# mcdm_v52.net
KiCad netlist of a schematic drawn in EAGLE
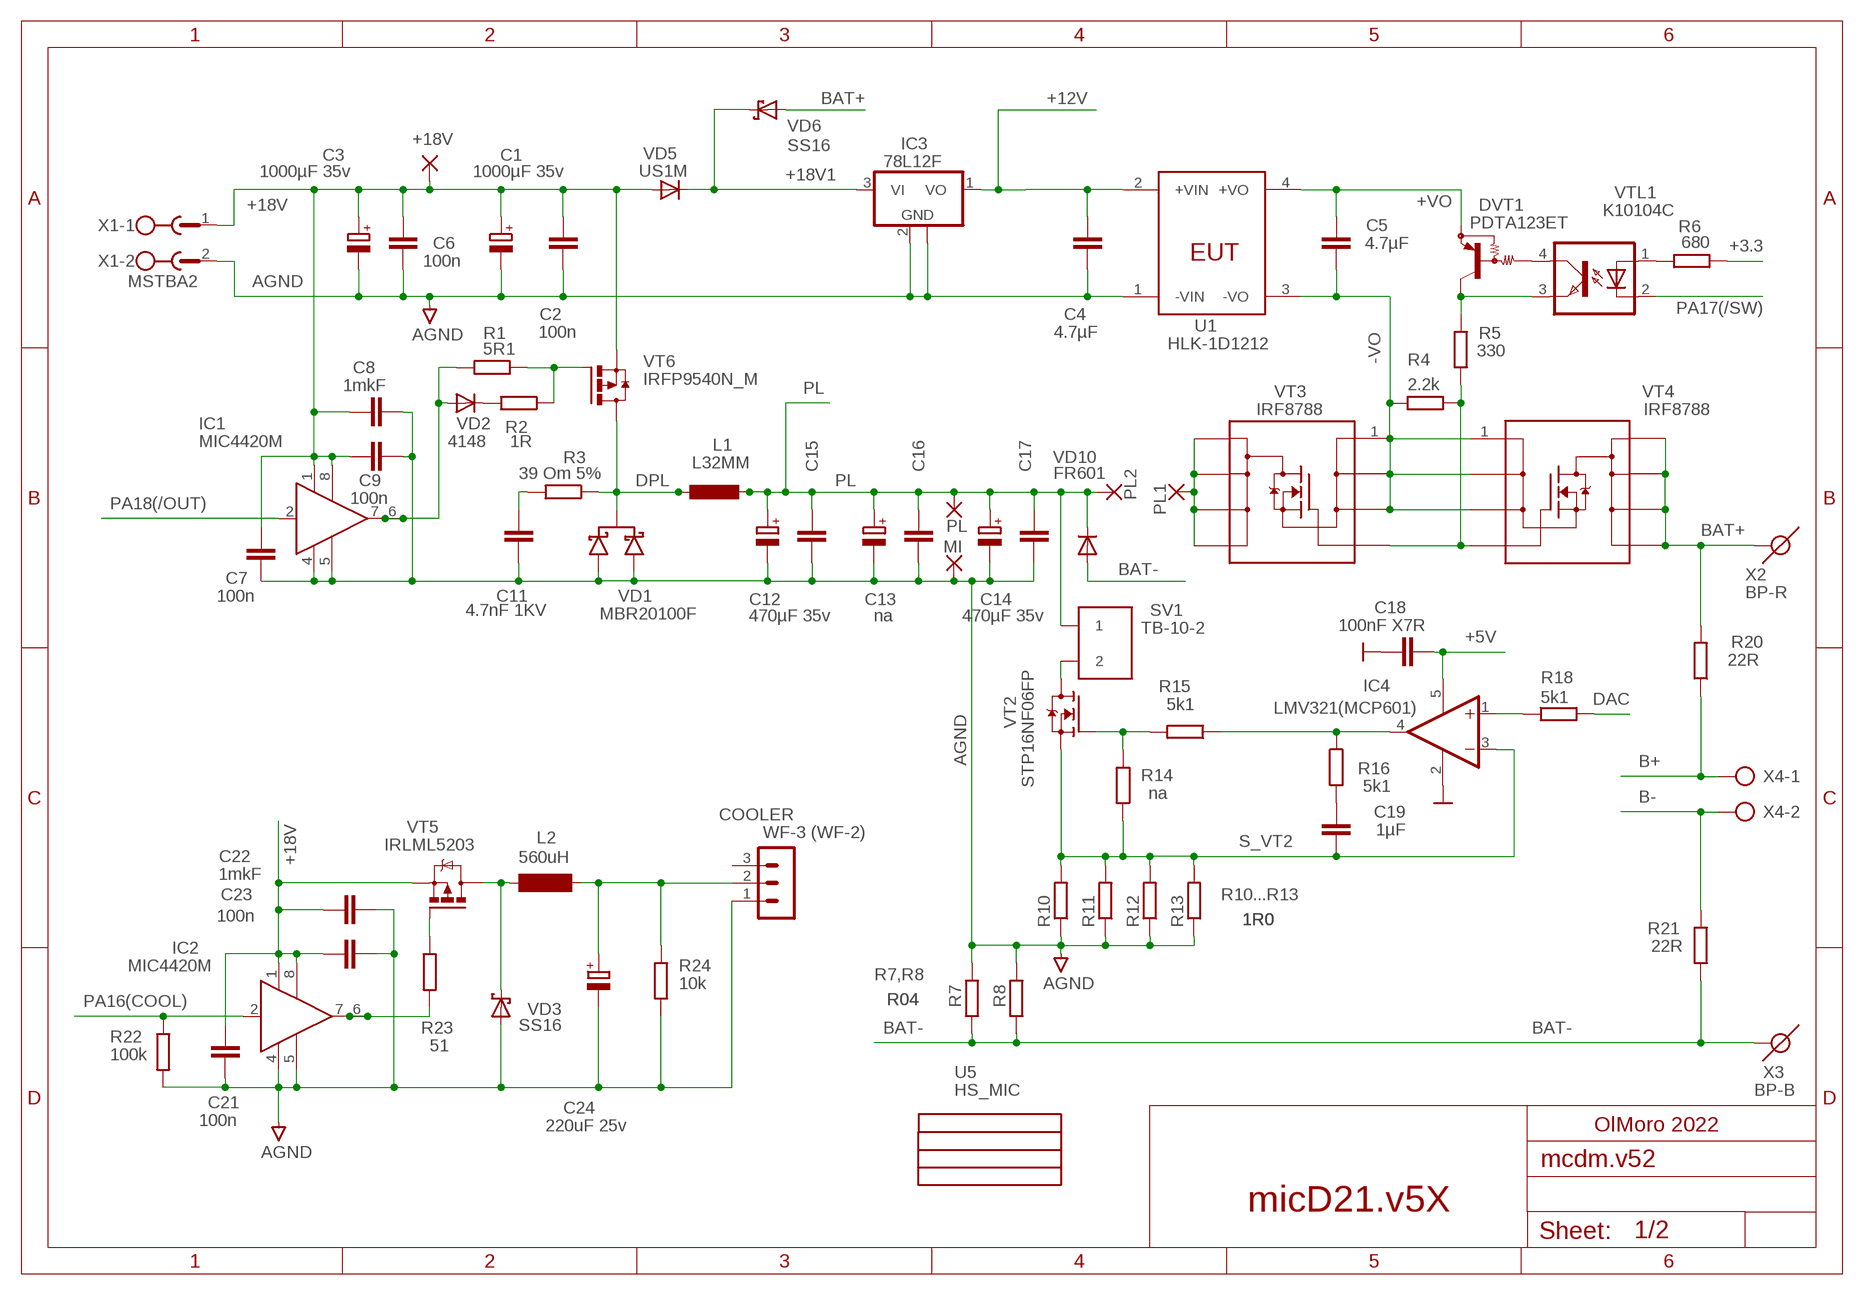
[diagram p0: schematic, sheet 1]
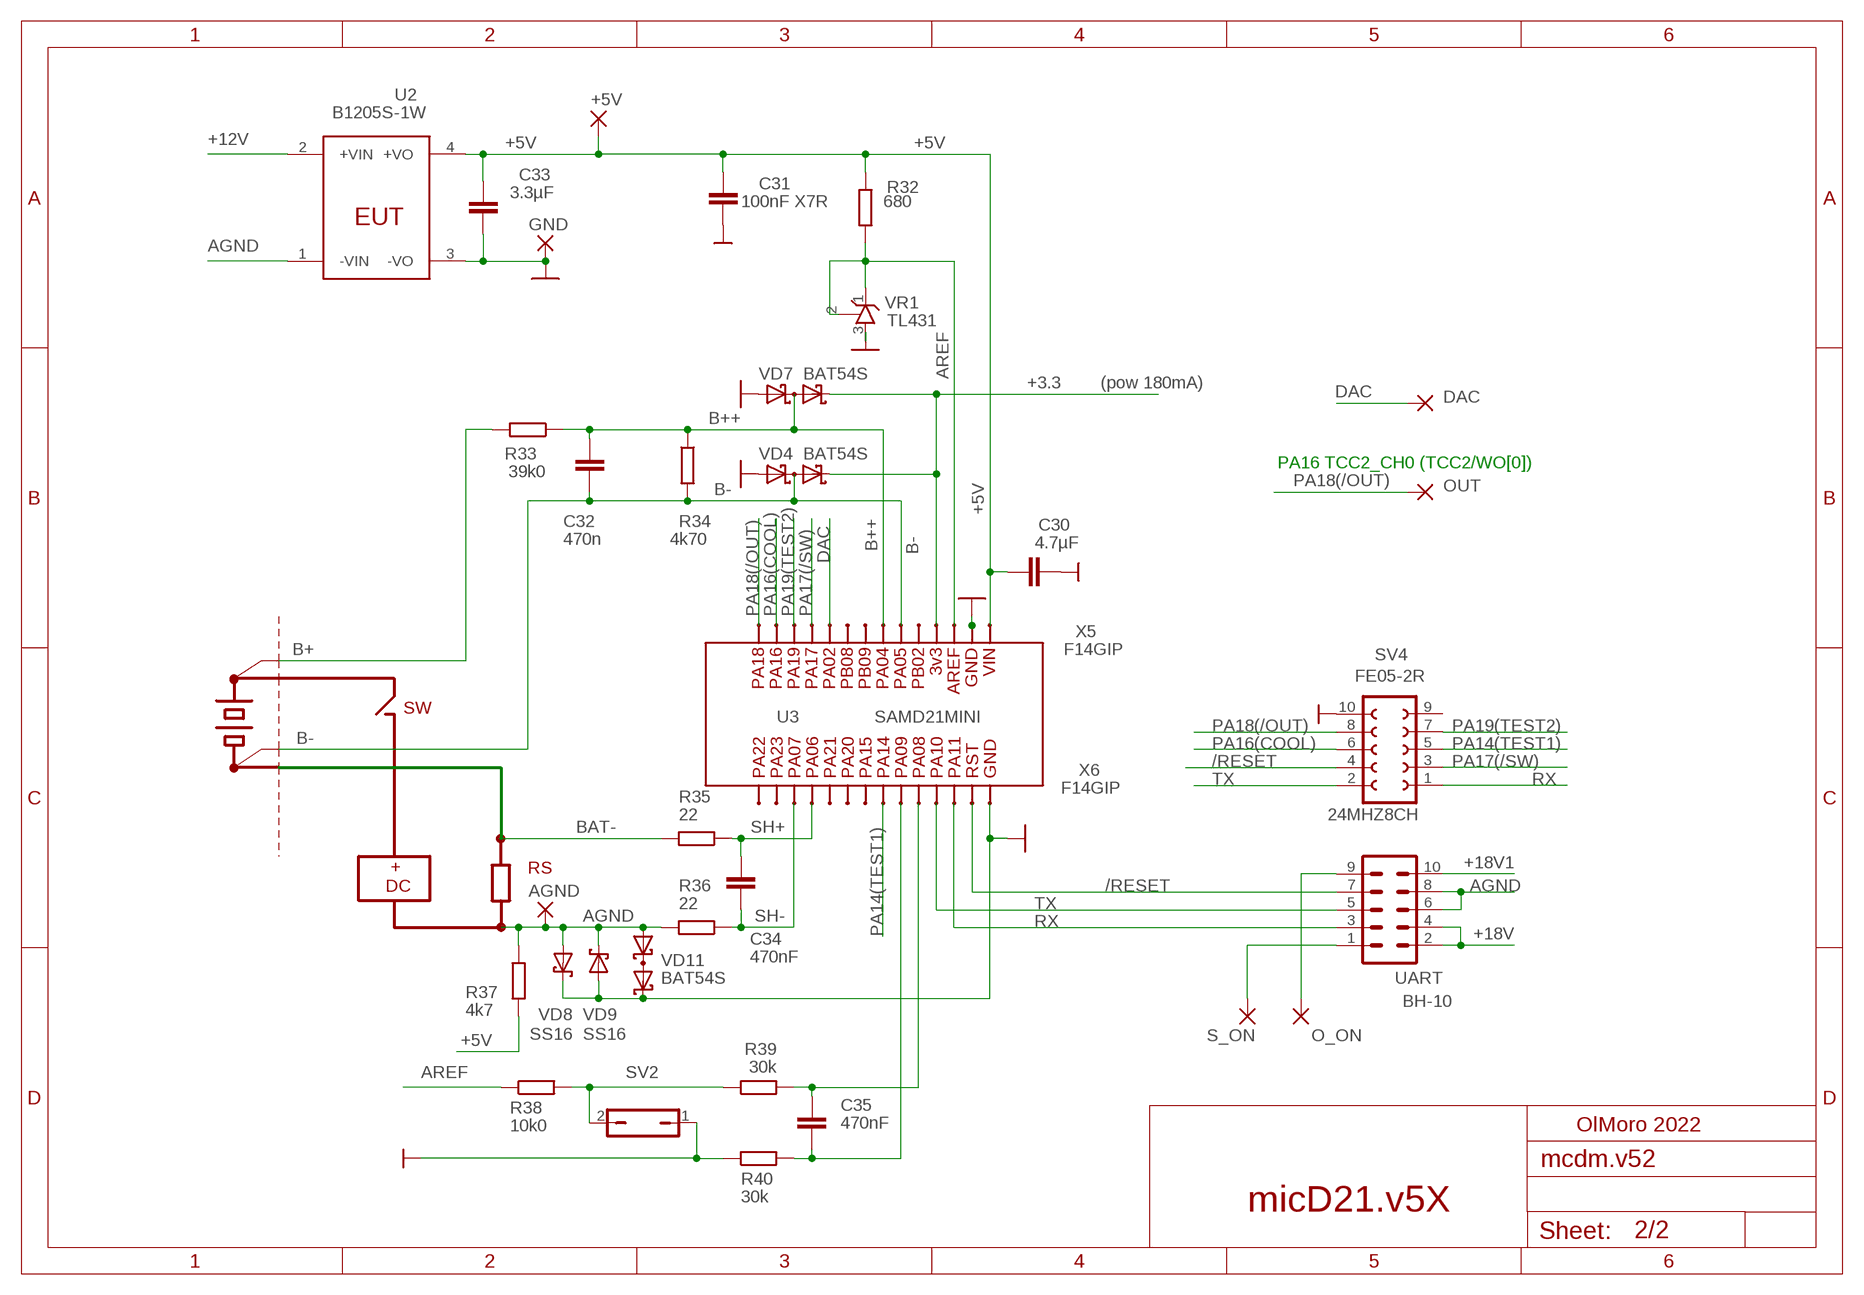
[diagram p1: schematic, sheet 2]

(export (version "E")
  (design (tool "Eeschema 10.0.6"))
  (components
    (comp (ref "+5V")
      (value "WIREPAD1,6/0,8")
      (footprint "eagle-import:1,6_0,8")
      (libsource (lib "eagle-import") (part "WIREPAD1,6/0,8"))
    )
    (comp (ref "24MHZ8CH")
      (value "DIAGNOSTICS")
      (footprint "eagle-import:DIAGNOSTICS")
      (libsource (lib "eagle-import") (part "DIAGNOSTICS"))
    )
    (comp (ref "AGND")
      (value "AGND")
      (footprint "eagle-import:4,16O1,6")
      (libsource (lib "eagle-import") (part "WIREPAD4,16O1,6"))
    )
    (comp (ref "C30")
      (value "4.7µF")
      (footprint "eagle-import:C0805")
      (libsource (lib "eagle-import") (part "C-EUC0805"))
    )
    (comp (ref "C31")
      (value "100nF X7R")
      (footprint "eagle-import:C0603")
      (libsource (lib "eagle-import") (part "C-EUC0603"))
    )
    (comp (ref "C32")
      (value "470n")
      (footprint "eagle-import:C0603")
      (libsource (lib "eagle-import") (part "C-EUC0603"))
    )
    (comp (ref "C33")
      (value "3.3µF")
      (footprint "eagle-import:C0805")
      (libsource (lib "eagle-import") (part "C-EUC0805"))
    )
    (comp (ref "C34")
      (value "470nF")
      (footprint "eagle-import:C0603")
      (libsource (lib "eagle-import") (part "C-EUC0603"))
    )
    (comp (ref "C35")
      (value "470nF")
      (footprint "eagle-import:C0603")
      (libsource (lib "eagle-import") (part "C-EUC0603"))
    )
    (comp (ref "DAC")
      (value "WIREPAD1,6/0,8")
      (footprint "eagle-import:1,6_0,8")
      (libsource (lib "eagle-import") (part "WIREPAD1,6/0,8"))
    )
    (comp (ref "GND")
      (value "GND")
      (footprint "eagle-import:4,16O1,6")
      (libsource (lib "eagle-import") (part "WIREPAD4,16O1,6"))
    )
    (comp (ref "OUT")
      (value "WIREPAD1,6/0,8")
      (footprint "eagle-import:1,6_0,8")
      (libsource (lib "eagle-import") (part "WIREPAD1,6/0,8"))
    )
    (comp (ref "O_ON")
      (value "WIREPAD1,6/0,8")
      (footprint "eagle-import:1,6_0,8")
      (libsource (lib "eagle-import") (part "WIREPAD1,6/0,8"))
    )
    (comp (ref "R32")
      (value "680")
      (footprint "eagle-import:R0603")
      (libsource (lib "eagle-import") (part "R-EU_R0603"))
    )
    (comp (ref "R33")
      (value "39k0")
      (footprint "eagle-import:R0603")
      (libsource (lib "eagle-import") (part "R-EU_R0603"))
    )
    (comp (ref "R34")
      (value "4k70")
      (footprint "eagle-import:R0603")
      (libsource (lib "eagle-import") (part "R-EU_R0603"))
    )
    (comp (ref "R35")
      (value "22")
      (footprint "eagle-import:R0603")
      (libsource (lib "eagle-import") (part "R-EU_R0603"))
    )
    (comp (ref "R36")
      (value "22")
      (footprint "eagle-import:R0603")
      (libsource (lib "eagle-import") (part "R-EU_R0603"))
    )
    (comp (ref "R37")
      (value "4k7")
      (footprint "eagle-import:R0603")
      (libsource (lib "eagle-import") (part "R-EU_R0603"))
    )
    (comp (ref "R38")
      (value "10k0")
      (footprint "eagle-import:R0603")
      (libsource (lib "eagle-import") (part "R-EU_R0603"))
    )
    (comp (ref "R39")
      (value "30k")
      (footprint "eagle-import:R0603")
      (libsource (lib "eagle-import") (part "R-EU_R0603"))
    )
    (comp (ref "R40")
      (value "30k")
      (footprint "eagle-import:R0603")
      (libsource (lib "eagle-import") (part "R-EU_R0603"))
    )
    (comp (ref "SV2")
      (value "JP1Q")
      (footprint "eagle-import:JP1")
      (libsource (lib "eagle-import") (part "JP1Q"))
    )
    (comp (ref "SV4")
      (value "FE05-2R")
      (footprint "eagle-import:FE05-2R")
      (libsource (lib "eagle-import") (part "FE05-2R"))
    )
    (comp (ref "S_ON")
      (value "WIREPAD1,6/0,8")
      (footprint "eagle-import:1,6_0,8")
      (libsource (lib "eagle-import") (part "WIREPAD1,6/0,8"))
    )
    (comp (ref "U2")
      (value "B1205S-1W")
      (footprint "eagle-import:HLK-1D1212")
      (libsource (lib "eagle-import") (part "HLK-1D1212"))
    )
    (comp (ref "U3")
      (value "SAMD21MINI")
      (footprint "eagle-import:SAMD21MINI")
      (libsource (lib "eagle-import") (part "SAMD21MINI"))
    )
    (comp (ref "UART")
      (value "BH-10")
      (footprint "eagle-import:ML10")
      (libsource (lib "eagle-import") (part "ML10"))
    )
    (comp (ref "VD4")
      (value "BAT54S")
      (footprint "eagle-import:SOT23")
      (libsource (lib "eagle-import") (part "BAT54S"))
    )
    (comp (ref "VD7")
      (value "BAT54S")
      (footprint "eagle-import:SOT23")
      (libsource (lib "eagle-import") (part "BAT54S"))
    )
    (comp (ref "VD8")
      (value "SS16")
      (footprint "eagle-import:DO214AC")
      (libsource (lib "eagle-import") (part "SS16"))
    )
    (comp (ref "VD9")
      (value "SS16")
      (footprint "eagle-import:DO214AC")
      (libsource (lib "eagle-import") (part "SS16"))
    )
    (comp (ref "VD11")
      (value "BAT54S")
      (footprint "eagle-import:SOT23")
      (libsource (lib "eagle-import") (part "BAT54S"))
    )
    (comp (ref "VR1")
      (value "TL431")
      (footprint "eagle-import:SOT23")
      (libsource (lib "eagle-import") (part "TL431-SOT23-3"))
    )
    (comp (ref "X5")
      (value "F14GIP")
      (footprint "eagle-import:F14GIP")
      (libsource (lib "eagle-import") (part "F14GIP"))
    )
    (comp (ref "X6")
      (value "F14GIP")
      (footprint "eagle-import:F14GIP")
      (libsource (lib "eagle-import") (part "F14GIP"))
    )
    (comp (ref "+18V")
      (value "WIREPAD1,6/0,8")
      (footprint "eagle-import:1,6_0,8")
      (libsource (lib "eagle-import") (part "WIREPAD1,6/0,8"))
    )
    (comp (ref "C1")
      (value "1000µF 35v")
      (footprint "eagle-import:E5-10,5")
      (libsource (lib "eagle-import") (part "CPOL-EUE5-10.5"))
    )
    (comp (ref "C2")
      (value "100n")
      (footprint "eagle-import:C0805")
      (libsource (lib "eagle-import") (part "C-EUC0805"))
    )
    (comp (ref "C3")
      (value "1000µF 35v")
      (footprint "eagle-import:E5-10,5")
      (libsource (lib "eagle-import") (part "CPOL-EUE5-10.5"))
    )
    (comp (ref "C4")
      (value "4.7µF")
      (footprint "eagle-import:C0603")
      (libsource (lib "eagle-import") (part "C-EUC0603"))
    )
    (comp (ref "C5")
      (value "4.7µF")
      (footprint "eagle-import:C0603")
      (libsource (lib "eagle-import") (part "C-EUC0603"))
    )
    (comp (ref "C6")
      (value "100n")
      (footprint "eagle-import:C0805")
      (libsource (lib "eagle-import") (part "C-EUC0805"))
    )
    (comp (ref "C7")
      (value "100n")
      (footprint "eagle-import:C0603")
      (libsource (lib "eagle-import") (part "C-EUC0603"))
    )
    (comp (ref "C8")
      (value "1mkF")
      (footprint "eagle-import:C0603")
      (libsource (lib "eagle-import") (part "C-EUC0603"))
    )
    (comp (ref "C9")
      (value "100n")
      (footprint "eagle-import:C0603")
      (libsource (lib "eagle-import") (part "C-EUC0603"))
    )
    (comp (ref "C11")
      (value "4.7nF 1KV")
      (footprint "eagle-import:C102-064X133")
      (libsource (lib "eagle-import") (part "C-EU102-064X133"))
    )
    (comp (ref "C12")
      (value "470µF 35v")
      (footprint "eagle-import:E5-10,5")
      (libsource (lib "eagle-import") (part "CPOL-EUE5-10.5"))
    )
    (comp (ref "C13")
      (value "na")
      (footprint "eagle-import:E5-10,5")
      (libsource (lib "eagle-import") (part "CPOL-EUE5-10.5"))
    )
    (comp (ref "C14")
      (value "470µF 35v")
      (footprint "eagle-import:E5-10,5")
      (libsource (lib "eagle-import") (part "CPOL-EUE5-10.5"))
    )
    (comp (ref "C15")
      (value "1mkF")
      (footprint "eagle-import:C0805")
      (libsource (lib "eagle-import") (part "C-EUC0805"))
    )
    (comp (ref "C16")
      (value "1mkF")
      (footprint "eagle-import:C0805")
      (libsource (lib "eagle-import") (part "C-EUC0805"))
    )
    (comp (ref "C17")
      (value "1mkF")
      (footprint "eagle-import:C0805")
      (libsource (lib "eagle-import") (part "C-EUC0805"))
    )
    (comp (ref "C18")
      (value "100nF X7R")
      (footprint "eagle-import:C0603")
      (libsource (lib "eagle-import") (part "C-EUC0603"))
    )
    (comp (ref "C19")
      (value "1µF")
      (footprint "eagle-import:C0603")
      (libsource (lib "eagle-import") (part "C-EUC0603"))
    )
    (comp (ref "C21")
      (value "100n")
      (footprint "eagle-import:C0603")
      (libsource (lib "eagle-import") (part "C-EUC0603"))
    )
    (comp (ref "C22")
      (value "1mkF")
      (footprint "eagle-import:C0603")
      (libsource (lib "eagle-import") (part "C-EUC0603"))
    )
    (comp (ref "C23")
      (value "100n")
      (footprint "eagle-import:C0603")
      (libsource (lib "eagle-import") (part "C-EUC0603"))
    )
    (comp (ref "C24")
      (value "220uF 25v")
      (footprint "eagle-import:E5-8,5")
      (libsource (lib "eagle-import") (part "CPOL-EUE5-8.5"))
    )
    (comp (ref "COOLER")
      (value "WF-3 (WF-2)")
      (footprint "eagle-import:WF-3")
      (libsource (lib "eagle-import") (part "WF-3"))
    )
    (comp (ref "DVT1")
      (value "PDTA123ET")
      (footprint "eagle-import:SC59-BEC")
      (libsource (lib "eagle-import") (part "MUN2113T1"))
    )
    (comp (ref "IC1")
      (value "MIC4420M")
      (footprint "eagle-import:SO-08")
      (libsource (lib "eagle-import") (part "MIC4420M"))
    )
    (comp (ref "IC2")
      (value "MIC4420M")
      (footprint "eagle-import:SO-08")
      (libsource (lib "eagle-import") (part "MIC4420M"))
    )
    (comp (ref "IC3")
      (value "78L12F")
      (footprint "eagle-import:SOT89")
      (libsource (lib "eagle-import") (part "78LF12"))
    )
    (comp (ref "IC4")
      (value "LMV321(MCP601)")
      (footprint "eagle-import:SOT23-5")
      (libsource (lib "eagle-import") (part "LM321?MF"))
    )
    (comp (ref "L1")
      (value "L32MM")
      (footprint "eagle-import:L22MM")
      (libsource (lib "eagle-import") (part "L32MM"))
    )
    (comp (ref "L2")
      (value "560uH")
      (footprint "eagle-import:BS11")
      (libsource (lib "eagle-import") (part "BS11"))
    )
    (comp (ref "MI")
      (value "WIREPAD4,16O1,6")
      (footprint "eagle-import:4,16O1,6")
      (libsource (lib "eagle-import") (part "WIREPAD4,16O1,6"))
    )
    (comp (ref "PL")
      (value "WIREPAD4,16O1,6")
      (footprint "eagle-import:4,16O1,6")
      (libsource (lib "eagle-import") (part "WIREPAD4,16O1,6"))
    )
    (comp (ref "PL1")
      (value "WIREPAD2,54/0,8")
      (footprint "eagle-import:2,54_0,8")
      (libsource (lib "eagle-import") (part "WIREPAD2,54/0,8"))
    )
    (comp (ref "PL2")
      (value "WIREPAD2,54/0,8")
      (footprint "eagle-import:2,54_0,8")
      (libsource (lib "eagle-import") (part "WIREPAD2,54/0,8"))
    )
    (comp (ref "R1")
      (value "5R1")
      (footprint "eagle-import:R0805")
      (libsource (lib "eagle-import") (part "R-EU_R0805"))
    )
    (comp (ref "R2")
      (value "1R")
      (footprint "eagle-import:R0805")
      (libsource (lib "eagle-import") (part "R-EU_R0805"))
    )
    (comp (ref "R3")
      (value "39 Om 5%")
      (footprint "eagle-import:0515_20")
      (libsource (lib "eagle-import") (part "R-0515/20"))
    )
    (comp (ref "R4")
      (value "2.2k")
      (footprint "eagle-import:R0603")
      (libsource (lib "eagle-import") (part "R-EU_R0603"))
    )
    (comp (ref "R5")
      (value "330")
      (footprint "eagle-import:R0603")
      (libsource (lib "eagle-import") (part "R-EU_R0603"))
    )
    (comp (ref "R6")
      (value "680")
      (footprint "eagle-import:R0603")
      (libsource (lib "eagle-import") (part "R-EU_R0603"))
    )
    (comp (ref "R7")
      (value "R04")
      (footprint "eagle-import:R2512")
      (libsource (lib "eagle-import") (part "R-EU_R2512"))
    )
    (comp (ref "R8")
      (value "R04")
      (footprint "eagle-import:R2512")
      (libsource (lib "eagle-import") (part "R-EU_R2512"))
    )
    (comp (ref "R10")
      (value "1R0")
      (footprint "eagle-import:R2512")
      (libsource (lib "eagle-import") (part "R-EU_R2512"))
    )
    (comp (ref "R11")
      (value "1R0")
      (footprint "eagle-import:R2512")
      (libsource (lib "eagle-import") (part "R-EU_R2512"))
    )
    (comp (ref "R12")
      (value "1R0")
      (footprint "eagle-import:R2512")
      (libsource (lib "eagle-import") (part "R-EU_R2512"))
    )
    (comp (ref "R13")
      (value "1R0")
      (footprint "eagle-import:R2512")
      (libsource (lib "eagle-import") (part "R-EU_R2512"))
    )
    (comp (ref "R14")
      (value "na")
      (footprint "eagle-import:R0603")
      (libsource (lib "eagle-import") (part "R-EU_R0603"))
    )
    (comp (ref "R15")
      (value "5k1")
      (footprint "eagle-import:R0603")
      (libsource (lib "eagle-import") (part "R-EU_R0603"))
    )
    (comp (ref "R16")
      (value "5k1")
      (footprint "eagle-import:R0603")
      (libsource (lib "eagle-import") (part "R-EU_R0603"))
    )
    (comp (ref "R18")
      (value "5k1")
      (footprint "eagle-import:R0603")
      (libsource (lib "eagle-import") (part "R-EU_R0603"))
    )
    (comp (ref "R20")
      (value "22R")
      (footprint "eagle-import:R0603")
      (libsource (lib "eagle-import") (part "R-EU_R0603"))
    )
    (comp (ref "R21")
      (value "22R")
      (footprint "eagle-import:R0603")
      (libsource (lib "eagle-import") (part "R-EU_R0603"))
    )
    (comp (ref "R22")
      (value "100k")
      (footprint "eagle-import:R0603")
      (libsource (lib "eagle-import") (part "R-EU_R0603"))
    )
    (comp (ref "R23")
      (value "51")
      (footprint "eagle-import:R0603")
      (libsource (lib "eagle-import") (part "R-EU_R0603"))
    )
    (comp (ref "R24")
      (value "10k")
      (footprint "eagle-import:R0603")
      (libsource (lib "eagle-import") (part "R-EU_R0603"))
    )
    (comp (ref "SV1")
      (value "TB-10-2")
      (footprint "eagle-import:TB-10-2")
      (libsource (lib "eagle-import") (part "TB-10-2"))
    )
    (comp (ref "U1")
      (value "HLK-1D1212")
      (footprint "eagle-import:HLK-1D1212")
      (libsource (lib "eagle-import") (part "HLK-1D1212"))
    )
    (comp (ref "U5")
      (value "HS_MIC")
      (footprint "eagle-import:HS-MIC")
      (libsource (lib "eagle-import") (part "HS_MIC"))
    )
    (comp (ref "VD1")
      (value "MBR20100F")
      (footprint "eagle-import:ITO220J")
      (libsource (lib "eagle-import") (part "MBR20100F"))
    )
    (comp (ref "VD2")
      (value "4148")
      (footprint "eagle-import:SMADIODE")
      (libsource (lib "eagle-import") (part "DIODESMA"))
    )
    (comp (ref "VD3")
      (value "SS16")
      (footprint "eagle-import:DO214AC")
      (libsource (lib "eagle-import") (part "SS16"))
    )
    (comp (ref "VD5")
      (value "US1M")
      (footprint "eagle-import:DO214AC")
      (libsource (lib "eagle-import") (part "US1M"))
    )
    (comp (ref "VD6")
      (value "SS16")
      (footprint "eagle-import:DO214AC")
      (libsource (lib "eagle-import") (part "SS16"))
    )
    (comp (ref "VD10")
      (value "FR601")
      (footprint "eagle-import:DIODE-1_P6-15")
      (libsource (lib "eagle-import") (part "DIODE-1_DIODE-P6-15"))
    )
    (comp (ref "VT2")
      (value "STP16NF06FP")
      (footprint "eagle-import:TO-220FP_M")
      (libsource (lib "eagle-import") (part "STP16NF06FP"))
    )
    (comp (ref "VT3")
      (value "IRF8788")
      (footprint "eagle-import:SO-8")
      (libsource (lib "eagle-import") (part "IRF8788"))
    )
    (comp (ref "VT4")
      (value "IRF8788")
      (footprint "eagle-import:SO-8")
      (libsource (lib "eagle-import") (part "IRF8788"))
    )
    (comp (ref "VT5")
      (value "IRLML5203")
      (footprint "eagle-import:MICRO3")
      (libsource (lib "eagle-import") (part "IRLML5203"))
    )
    (comp (ref "VT6")
      (value "IRFP9540N_M")
      (footprint "eagle-import:TO-220FP_M")
      (libsource (lib "eagle-import") (part "IRFP9540N_M"))
    )
    (comp (ref "VTL1")
      (value "K10104C")
      (footprint "eagle-import:SMD4-7")
      (libsource (lib "eagle-import") (part "SFH618?A-3X007"))
    )
    (comp (ref "X1")
      (value "MSTBA2")
      (footprint "eagle-import:MSTBA2")
      (fields (field (name "MF") "FARNELL") (field (name "MPN") "1757242"))
      (libsource (lib "eagle-import") (part "MSTBA2"))
    )
    (comp (ref "X2")
      (value "BP-R")
      (footprint "eagle-import:BP-R")
      (libsource (lib "eagle-import") (part "BP-R"))
    )
    (comp (ref "X3")
      (value "BP-B")
      (footprint "eagle-import:BP-B")
      (libsource (lib "eagle-import") (part "BP-B"))
    )
    (comp (ref "X4")
      (value "AK500/2-H")
      (footprint "eagle-import:AK500_2-H")
      (libsource (lib "eagle-import") (part "AK500/2-H"))
    )
  )
  (nets
    (net (code "1") (name "+3.3") (class "Default")
      (node (ref "R6") (pin "1") (pinfunction "1_1") (pintype "passive"))
      (node (ref "VD4") (pin "2") (pinfunction "C2_2") (pintype "passive"))
      (node (ref "VD7") (pin "2") (pinfunction "C2_2") (pintype "passive"))
      (node (ref "X5") (pin "4") (pinfunction "4_4") (pintype "passive"))
    )
    (net (code "2") (name "+5V") (class "Default")
      (node (ref "+5V") (pin "1") (pinfunction "P_1") (pintype "passive"))
      (node (ref "C18") (pin "2") (pinfunction "2_2") (pintype "passive"))
      (node (ref "C30") (pin "1") (pinfunction "1_1") (pintype "passive"))
      (node (ref "C31") (pin "1") (pinfunction "1_1") (pintype "passive"))
      (node (ref "C33") (pin "1") (pinfunction "1_1") (pintype "passive"))
      (node (ref "IC4") (pin "5") (pinfunction "V+_5") (pintype "power_in"))
      (node (ref "R32") (pin "1") (pinfunction "1_1") (pintype "passive"))
      (node (ref "R37") (pin "2") (pinfunction "2_2") (pintype "passive"))
      (node (ref "U2") (pin "4") (pinfunction "+VO_4") (pintype "power_in"))
      (node (ref "X5") (pin "1") (pinfunction "1_1") (pintype "passive"))
    )
    (net (code "3") (name "+12V") (class "Default")
      (node (ref "C4") (pin "2") (pinfunction "2_2") (pintype "passive"))
      (node (ref "IC3") (pin "1") (pinfunction "VO_1") (pintype "passive"))
      (node (ref "U1") (pin "2") (pinfunction "+VIN_2") (pintype "power_in"))
      (node (ref "U2") (pin "2") (pinfunction "+VIN_2") (pintype "power_in"))
    )
    (net (code "4") (name "+18V") (class "Default")
      (node (ref "+18V") (pin "1") (pinfunction "P_1") (pintype "passive"))
      (node (ref "C1") (pin "+") (pinfunction "+_+") (pintype "passive"))
      (node (ref "C2") (pin "2") (pinfunction "2_2") (pintype "passive"))
      (node (ref "C21") (pin "2") (pinfunction "2_2") (pintype "passive"))
      (node (ref "C22") (pin "2") (pinfunction "2_2") (pintype "passive"))
      (node (ref "C23") (pin "2") (pinfunction "2_2") (pintype "passive"))
      (node (ref "C3") (pin "+") (pinfunction "+_+") (pintype "passive"))
      (node (ref "C6") (pin "2") (pinfunction "2_2") (pintype "passive"))
      (node (ref "C7") (pin "2") (pinfunction "2_2") (pintype "passive"))
      (node (ref "C8") (pin "2") (pinfunction "2_2") (pintype "passive"))
      (node (ref "C9") (pin "2") (pinfunction "2_2") (pintype "passive"))
      (node (ref "IC1") (pin "1") (pinfunction "VS_1") (pintype "power_in"))
      (node (ref "IC1") (pin "8") (pinfunction "VS1_8") (pintype "power_in"))
      (node (ref "IC2") (pin "1") (pinfunction "VS_1") (pintype "power_in"))
      (node (ref "IC2") (pin "8") (pinfunction "VS1_8") (pintype "power_in"))
      (node (ref "UART") (pin "2") (pinfunction "2_2") (pintype "passive"))
      (node (ref "UART") (pin "4") (pinfunction "4_4") (pintype "passive"))
      (node (ref "VD5") (pin "A") (pinfunction "A_A") (pintype "passive"))
      (node (ref "VT5") (pin "2") (pinfunction "S_2") (pintype "passive"))
      (node (ref "VT6") (pin "3") (pinfunction "S_3") (pintype "passive"))
      (node (ref "X1") (pin "1") (pinfunction "1_1") (pintype "passive"))
    )
    (net (code "5") (name "+18V1") (class "Default")
      (node (ref "IC3") (pin "3") (pinfunction "VI_3") (pintype "input"))
      (node (ref "UART") (pin "10") (pinfunction "10_10") (pintype "passive"))
      (node (ref "VD5") (pin "C") (pinfunction "C_C") (pintype "passive"))
      (node (ref "VD6") (pin "C") (pinfunction "C_C") (pintype "passive"))
    )
    (net (code "6") (name "+VO") (class "Default")
      (node (ref "C5") (pin "2") (pinfunction "2_2") (pintype "passive"))
      (node (ref "DVT1") (pin "E") (pinfunction "E_E") (pintype "passive"))
      (node (ref "U1") (pin "4") (pinfunction "+VO_4") (pintype "power_in"))
    )
    (net (code "7") (name "-VO") (class "Default")
      (node (ref "C5") (pin "1") (pinfunction "1_1") (pintype "passive"))
      (node (ref "R4") (pin "2") (pinfunction "2_2") (pintype "passive"))
      (node (ref "U1") (pin "3") (pinfunction "-VO_3") (pintype "power_in"))
      (node (ref "VT3") (pin "1") (pinfunction "S_1") (pintype "passive"))
      (node (ref "VT3") (pin "2") (pinfunction "S_2") (pintype "passive"))
      (node (ref "VT3") (pin "3") (pinfunction "S_3") (pintype "passive"))
      (node (ref "VT4") (pin "1") (pinfunction "S_1") (pintype "passive"))
      (node (ref "VT4") (pin "2") (pinfunction "S_2") (pintype "passive"))
      (node (ref "VT4") (pin "3") (pinfunction "S_3") (pintype "passive"))
    )
    (net (code "8") (name "AGND") (class "Default")
      (node (ref "AGND") (pin "1") (pinfunction "P_1") (pintype "passive"))
      (node (ref "C1") (pin "-") (pinfunction "-_-") (pintype "passive"))
      (node (ref "C11") (pin "2") (pinfunction "2_2") (pintype "passive"))
      (node (ref "C12") (pin "-") (pinfunction "-_-") (pintype "passive"))
      (node (ref "C13") (pin "-") (pinfunction "-_-") (pintype "passive"))
      (node (ref "C14") (pin "-") (pinfunction "-_-") (pintype "passive"))
      (node (ref "C15") (pin "2") (pinfunction "2_2") (pintype "passive"))
      (node (ref "C16") (pin "2") (pinfunction "2_2") (pintype "passive"))
      (node (ref "C17") (pin "2") (pinfunction "2_2") (pintype "passive"))
      (node (ref "C2") (pin "1") (pinfunction "1_1") (pintype "passive"))
      (node (ref "C21") (pin "1") (pinfunction "1_1") (pintype "passive"))
      (node (ref "C22") (pin "1") (pinfunction "1_1") (pintype "passive"))
      (node (ref "C23") (pin "1") (pinfunction "1_1") (pintype "passive"))
      (node (ref "C24") (pin "-") (pinfunction "-_-") (pintype "passive"))
      (node (ref "C3") (pin "-") (pinfunction "-_-") (pintype "passive"))
      (node (ref "C4") (pin "1") (pinfunction "1_1") (pintype "passive"))
      (node (ref "C6") (pin "1") (pinfunction "1_1") (pintype "passive"))
      (node (ref "C7") (pin "1") (pinfunction "1_1") (pintype "passive"))
      (node (ref "C8") (pin "1") (pinfunction "1_1") (pintype "passive"))
      (node (ref "C9") (pin "1") (pinfunction "1_1") (pintype "passive"))
      (node (ref "COOLER") (pin "1") (pinfunction "1_1") (pintype "passive"))
      (node (ref "IC1") (pin "4") (pinfunction "GND_4") (pintype "power_in"))
      (node (ref "IC1") (pin "5") (pinfunction "GND1_5") (pintype "power_in"))
      (node (ref "IC2") (pin "4") (pinfunction "GND_4") (pintype "power_in"))
      (node (ref "IC2") (pin "5") (pinfunction "GND1_5") (pintype "power_in"))
      (node (ref "IC3") (pin "2") (pinfunction "GND_2") (pintype "passive"))
      (node (ref "IC3") (pin "2@1") (pinfunction "GND_2@1") (pintype "passive"))
      (node (ref "MI") (pin "1") (pinfunction "P_1") (pintype "passive"))
      (node (ref "R10") (pin "1") (pinfunction "1_1") (pintype "passive"))
      (node (ref "R11") (pin "1") (pinfunction "1_1") (pintype "passive"))
      (node (ref "R12") (pin "1") (pinfunction "1_1") (pintype "passive"))
      (node (ref "R13") (pin "1") (pinfunction "1_1") (pintype "passive"))
      (node (ref "R22") (pin "2") (pinfunction "2_2") (pintype "passive"))
      (node (ref "R24") (pin "2") (pinfunction "2_2") (pintype "passive"))
      (node (ref "R36") (pin "2") (pinfunction "2_2") (pintype "passive"))
      (node (ref "R37") (pin "1") (pinfunction "1_1") (pintype "passive"))
      (node (ref "R7") (pin "2") (pinfunction "2_2") (pintype "passive"))
      (node (ref "R8") (pin "2") (pinfunction "2_2") (pintype "passive"))
      (node (ref "U1") (pin "1") (pinfunction "-VIN_1") (pintype "power_in"))
      (node (ref "U2") (pin "1") (pinfunction "-VIN_1") (pintype "power_in"))
      (node (ref "UART") (pin "6") (pinfunction "6_6") (pintype "passive"))
      (node (ref "UART") (pin "8") (pinfunction "8_8") (pintype "passive"))
      (node (ref "VD1") (pin "1") (pinfunction "A1_1") (pintype "passive"))
      (node (ref "VD1") (pin "3") (pinfunction "A2_3") (pintype "passive"))
      (node (ref "VD11") (pin "1") (pinfunction "A1_1") (pintype "passive"))
      (node (ref "VD3") (pin "A") (pinfunction "A_A") (pintype "passive"))
      (node (ref "VD8") (pin "A") (pinfunction "A_A") (pintype "passive"))
      (node (ref "VD9") (pin "C") (pinfunction "C_C") (pintype "passive"))
      (node (ref "X1") (pin "2") (pinfunction "1_2") (pintype "passive"))
    )
    (net (code "9") (name "AREF") (class "Default")
      (node (ref "R32") (pin "2") (pinfunction "2_2") (pintype "passive"))
      (node (ref "R38") (pin "1") (pinfunction "1_1") (pintype "passive"))
      (node (ref "VR1") (pin "1") (pinfunction "C_1") (pintype "passive"))
      (node (ref "VR1") (pin "2") (pinfunction "R_2") (pintype "passive"))
      (node (ref "X5") (pin "3") (pinfunction "3_3") (pintype "passive"))
    )
    (net (code "10") (name "B+") (class "Default")
      (node (ref "R20") (pin "1") (pinfunction "1_1") (pintype "passive"))
      (node (ref "R33") (pin "2") (pinfunction "2_2") (pintype "passive"))
      (node (ref "X4") (pin "1") (pinfunction "KL_1") (pintype "passive"))
    )
    (net (code "11") (name "B++") (class "Default")
      (node (ref "C32") (pin "1") (pinfunction "1_1") (pintype "passive"))
      (node (ref "R33") (pin "1") (pinfunction "1_1") (pintype "passive"))
      (node (ref "R34") (pin "1") (pinfunction "1_1") (pintype "passive"))
      (node (ref "VD7") (pin "3") (pinfunction "C1A2_3") (pintype "passive"))
      (node (ref "X5") (pin "7") (pinfunction "7_7") (pintype "passive"))
    )
    (net (code "12") (name "B-") (class "Default")
      (node (ref "C32") (pin "2") (pinfunction "2_2") (pintype "passive"))
      (node (ref "R21") (pin "1") (pinfunction "1_1") (pintype "passive"))
      (node (ref "R34") (pin "2") (pinfunction "2_2") (pintype "passive"))
      (node (ref "VD4") (pin "3") (pinfunction "C1A2_3") (pintype "passive"))
      (node (ref "X4") (pin "2") (pinfunction "KL_2") (pintype "passive"))
      (node (ref "X5") (pin "6") (pinfunction "6_6") (pintype "passive"))
    )
    (net (code "13") (name "BAT+") (class "Default")
      (node (ref "R20") (pin "2") (pinfunction "2_2") (pintype "passive"))
      (node (ref "VD6") (pin "A") (pinfunction "A_A") (pintype "passive"))
      (node (ref "VT4") (pin "5") (pinfunction "D_5") (pintype "passive"))
      (node (ref "VT4") (pin "6") (pinfunction "D_6") (pintype "passive"))
      (node (ref "VT4") (pin "7") (pinfunction "D_7") (pintype "passive"))
      (node (ref "VT4") (pin "8") (pinfunction "D_8") (pintype "passive"))
      (node (ref "X2") (pin "1") (pinfunction "P$1_1") (pintype "passive"))
    )
    (net (code "14") (name "BAT-") (class "Default")
      (node (ref "R21") (pin "2") (pinfunction "2_2") (pintype "passive"))
      (node (ref "R35") (pin "2") (pinfunction "2_2") (pintype "passive"))
      (node (ref "R7") (pin "1") (pinfunction "1_1") (pintype "passive"))
      (node (ref "R8") (pin "1") (pinfunction "1_1") (pintype "passive"))
      (node (ref "VD10") (pin "A") (pinfunction "A_A") (pintype "passive"))
      (node (ref "X3") (pin "1") (pinfunction "P$1_1") (pintype "passive"))
    )
    (net (code "15") (name "DAC") (class "Default")
      (node (ref "DAC") (pin "1") (pinfunction "P_1") (pintype "passive"))
      (node (ref "R18") (pin "2") (pinfunction "2_2") (pintype "passive"))
      (node (ref "X5") (pin "10") (pinfunction "10_10") (pintype "passive"))
    )
    (net (code "16") (name "DPL") (class "Default")
      (node (ref "L1") (pin "2@7") (pinfunction "2_2@7") (pintype "passive"))
      (node (ref "L1") (pin "2@8") (pinfunction "2_2@8") (pintype "passive"))
      (node (ref "R3") (pin "1") (pinfunction "1_1") (pintype "passive"))
      (node (ref "VD1") (pin "2") (pinfunction "C_2") (pintype "passive"))
      (node (ref "VT6") (pin "2") (pinfunction "D_2") (pintype "passive"))
    )
    (net (code "17") (name "GND") (class "Default")
      (node (ref "C18") (pin "1") (pinfunction "1_1") (pintype "passive"))
      (node (ref "C30") (pin "2") (pinfunction "2_2") (pintype "passive"))
      (node (ref "C31") (pin "2") (pinfunction "2_2") (pintype "passive"))
      (node (ref "C33") (pin "2") (pinfunction "2_2") (pintype "passive"))
      (node (ref "GND") (pin "1") (pinfunction "P_1") (pintype "passive"))
      (node (ref "IC4") (pin "2") (pinfunction "V-_2") (pintype "power_in"))
      (node (ref "R40") (pin "1") (pinfunction "1_1") (pintype "passive"))
      (node (ref "SV2") (pin "1") (pinfunction "1_1") (pintype "passive"))
      (node (ref "SV4") (pin "10") (pinfunction "10_10") (pintype "passive"))
      (node (ref "U2") (pin "3") (pinfunction "-VO_3") (pintype "power_in"))
      (node (ref "VD11") (pin "2") (pinfunction "C2_2") (pintype "passive"))
      (node (ref "VD4") (pin "1") (pinfunction "A1_1") (pintype "passive"))
      (node (ref "VD7") (pin "1") (pinfunction "A1_1") (pintype "passive"))
      (node (ref "VD8") (pin "C") (pinfunction "C_C") (pintype "passive"))
      (node (ref "VD9") (pin "A") (pinfunction "A_A") (pintype "passive"))
      (node (ref "VR1") (pin "3") (pinfunction "A_3") (pintype "passive"))
      (node (ref "X5") (pin "2") (pinfunction "2_2") (pintype "passive"))
      (node (ref "X6") (pin "14") (pinfunction "14_14") (pintype "passive"))
    )
    (net (code "18") (name "Net-(C11-Pad1)") (class "Default")
      (node (ref "C11") (pin "1") (pinfunction "1_1") (pintype "passive"))
      (node (ref "R3") (pin "2") (pinfunction "2_2") (pintype "passive"))
    )
    (net (code "19") (name "Net-(C19-Pad1)") (class "Default")
      (node (ref "C19") (pin "1") (pinfunction "1_1") (pintype "passive"))
      (node (ref "R16") (pin "2") (pinfunction "2_2") (pintype "passive"))
    )
    (net (code "20") (name "Net-(C24-Pad+)") (class "Default")
      (node (ref "C24") (pin "+") (pinfunction "+_+") (pintype "passive"))
      (node (ref "COOLER") (pin "2") (pinfunction "2_2") (pintype "passive"))
      (node (ref "L2") (pin "2") (pinfunction "2_2") (pintype "passive"))
      (node (ref "R24") (pin "1") (pinfunction "1_1") (pintype "passive"))
    )
    (net (code "21") (name "Net-(C35-Pad1)") (class "Default")
      (node (ref "C35") (pin "1") (pinfunction "1_1") (pintype "passive"))
      (node (ref "R39") (pin "2") (pinfunction "2_2") (pintype "passive"))
      (node (ref "X6") (pin "10") (pinfunction "10_10") (pintype "passive"))
    )
    (net (code "22") (name "Net-(C35-Pad2)") (class "Default")
      (node (ref "C35") (pin "2") (pinfunction "2_2") (pintype "passive"))
      (node (ref "R40") (pin "2") (pinfunction "2_2") (pintype "passive"))
      (node (ref "X6") (pin "9") (pinfunction "9_9") (pintype "passive"))
    )
    (net (code "23") (name "Net-(IC1-OUT-Pad6)") (class "Default")
      (node (ref "IC1") (pin "6") (pinfunction "OUT_6") (pintype "passive"))
      (node (ref "IC1") (pin "7") (pinfunction "OUT_7") (pintype "passive"))
      (node (ref "R1") (pin "2") (pinfunction "2_2") (pintype "passive"))
      (node (ref "VD2") (pin "A") (pinfunction "A_A") (pintype "passive"))
    )
    (net (code "24") (name "Net-(IC2-OUT-Pad6)") (class "Default")
      (node (ref "IC2") (pin "6") (pinfunction "OUT_6") (pintype "passive"))
      (node (ref "IC2") (pin "7") (pinfunction "OUT_7") (pintype "passive"))
      (node (ref "R23") (pin "2") (pinfunction "2_2") (pintype "passive"))
    )
    (net (code "25") (name "Net-(IC4-+IN)") (class "Default")
      (node (ref "IC4") (pin "1") (pinfunction "+IN_1") (pintype "input"))
      (node (ref "R18") (pin "1") (pinfunction "1_1") (pintype "passive"))
    )
    (net (code "26") (name "Net-(IC4-OUT)") (class "Default")
      (node (ref "IC4") (pin "4") (pinfunction "OUT_4") (pintype "output"))
      (node (ref "R15") (pin "1") (pinfunction "1_1") (pintype "passive"))
      (node (ref "R16") (pin "1") (pinfunction "1_1") (pintype "passive"))
    )
    (net (code "27") (name "Net-(O_ON-P)") (class "Default")
      (node (ref "O_ON") (pin "1") (pinfunction "P_1") (pintype "passive"))
      (node (ref "UART") (pin "9") (pinfunction "9_9") (pintype "passive"))
    )
    (net (code "28") (name "Net-(PL1-P)") (class "Default")
      (node (ref "PL1") (pin "1") (pinfunction "P_1") (pintype "passive"))
      (node (ref "VT3") (pin "5") (pinfunction "D_5") (pintype "passive"))
      (node (ref "VT3") (pin "6") (pinfunction "D_6") (pintype "passive"))
      (node (ref "VT3") (pin "7") (pinfunction "D_7") (pintype "passive"))
      (node (ref "VT3") (pin "8") (pinfunction "D_8") (pintype "passive"))
    )
    (net (code "29") (name "Net-(R2-Pad2)") (class "Default")
      (node (ref "R2") (pin "2") (pinfunction "2_2") (pintype "passive"))
      (node (ref "VD2") (pin "C") (pinfunction "C_C") (pintype "passive"))
    )
    (net (code "30") (name "Net-(R38-Pad2)") (class "Default")
      (node (ref "R38") (pin "2") (pinfunction "2_2") (pintype "passive"))
      (node (ref "R39") (pin "1") (pinfunction "1_1") (pintype "passive"))
      (node (ref "SV2") (pin "2") (pinfunction "2_2") (pintype "passive"))
    )
    (net (code "31") (name "Net-(SV1-2)") (class "Default")
      (node (ref "SV1") (pin "P$2") (pinfunction "2_P$2") (pintype "passive"))
      (node (ref "VT2") (pin "2") (pinfunction "D_2") (pintype "passive"))
    )
    (net (code "32") (name "Net-(S_ON-P)") (class "Default")
      (node (ref "S_ON") (pin "1") (pinfunction "P_1") (pintype "passive"))
      (node (ref "UART") (pin "1") (pinfunction "1_1") (pintype "passive"))
    )
    (net (code "33") (name "Net-(VT2-G)") (class "Default")
      (node (ref "R14") (pin "2") (pinfunction "2_2") (pintype "passive"))
      (node (ref "R15") (pin "2") (pinfunction "2_2") (pintype "passive"))
      (node (ref "VT2") (pin "1") (pinfunction "G_1") (pintype "passive"))
    )
    (net (code "34") (name "Net-(VT3-G)") (class "Default")
      (node (ref "R4") (pin "1") (pinfunction "1_1") (pintype "passive"))
      (node (ref "R5") (pin "1") (pinfunction "1_1") (pintype "passive"))
      (node (ref "VT3") (pin "4") (pinfunction "G_4") (pintype "passive"))
      (node (ref "VT4") (pin "4") (pinfunction "G_4") (pintype "passive"))
    )
    (net (code "35") (name "Net-(VT5-D)") (class "Default")
      (node (ref "L2") (pin "1") (pinfunction "1_1") (pintype "passive"))
      (node (ref "VD3") (pin "C") (pinfunction "C_C") (pintype "passive"))
      (node (ref "VT5") (pin "3") (pinfunction "D_3") (pintype "passive"))
    )
    (net (code "36") (name "Net-(VT5-G)") (class "Default")
      (node (ref "R23") (pin "1") (pinfunction "1_1") (pintype "passive"))
      (node (ref "VT5") (pin "1") (pinfunction "G_1") (pintype "passive"))
    )
    (net (code "37") (name "Net-(VT6-G)") (class "Default")
      (node (ref "R1") (pin "1") (pinfunction "1_1") (pintype "passive"))
      (node (ref "R2") (pin "1") (pinfunction "1_1") (pintype "passive"))
      (node (ref "VT6") (pin "1") (pinfunction "G_1") (pintype "passive"))
    )
    (net (code "38") (name "Net-(VTL1-A)") (class "Default")
      (node (ref "R6") (pin "2") (pinfunction "2_2") (pintype "passive"))
      (node (ref "VTL1") (pin "1") (pinfunction "A_1") (pintype "passive"))
    )
    (net (code "39") (name "Net-(VTL1-COL)") (class "Default")
      (node (ref "DVT1") (pin "B") (pinfunction "B_B") (pintype "passive"))
      (node (ref "VTL1") (pin "4") (pinfunction "COL_4") (pintype "passive"))
    )
    (net (code "40") (name "Net-(VTL1-EMIT)") (class "Default")
      (node (ref "DVT1") (pin "C") (pinfunction "C_C") (pintype "passive"))
      (node (ref "R5") (pin "2") (pinfunction "2_2") (pintype "passive"))
      (node (ref "VTL1") (pin "3") (pinfunction "EMIT_3") (pintype "passive"))
    )
    (net (code "41") (name "PA14(TEST1)") (class "Default")
      (node (ref "SV4") (pin "5") (pinfunction "5_5") (pintype "passive"))
      (node (ref "X6") (pin "8") (pinfunction "8_8") (pintype "passive"))
    )
    (net (code "42") (name "PA16(COOL)") (class "Default")
      (node (ref "IC2") (pin "2") (pinfunction "IN_2") (pintype "input"))
      (node (ref "R22") (pin "1") (pinfunction "1_1") (pintype "passive"))
      (node (ref "SV4") (pin "6") (pinfunction "6_6") (pintype "passive"))
      (node (ref "X5") (pin "13") (pinfunction "13_13") (pintype "passive"))
    )
    (net (code "43") (name "PA17({slash}SW)") (class "Default")
      (node (ref "SV4") (pin "3") (pinfunction "3_3") (pintype "passive"))
      (node (ref "VTL1") (pin "2") (pinfunction "C_2") (pintype "passive"))
      (node (ref "X5") (pin "11") (pinfunction "11_11") (pintype "passive"))
    )
    (net (code "44") (name "PA18({slash}OUT)") (class "Default")
      (node (ref "IC1") (pin "2") (pinfunction "IN_2") (pintype "input"))
      (node (ref "OUT") (pin "1") (pinfunction "P_1") (pintype "passive"))
      (node (ref "SV4") (pin "8") (pinfunction "8_8") (pintype "passive"))
      (node (ref "X5") (pin "14") (pinfunction "14_14") (pintype "passive"))
    )
    (net (code "45") (name "PA19(TEST2)") (class "Default")
      (node (ref "SV4") (pin "7") (pinfunction "7_7") (pintype "passive"))
      (node (ref "X5") (pin "12") (pinfunction "12_12") (pintype "passive"))
    )
    (net (code "46") (name "PL") (class "Default")
      (node (ref "C12") (pin "+") (pinfunction "+_+") (pintype "passive"))
      (node (ref "C13") (pin "+") (pinfunction "+_+") (pintype "passive"))
      (node (ref "C14") (pin "+") (pinfunction "+_+") (pintype "passive"))
      (node (ref "C15") (pin "1") (pinfunction "1_1") (pintype "passive"))
      (node (ref "C16") (pin "1") (pinfunction "1_1") (pintype "passive"))
      (node (ref "C17") (pin "1") (pinfunction "1_1") (pintype "passive"))
      (node (ref "L1") (pin "1") (pinfunction "1_1") (pintype "passive"))
      (node (ref "L1") (pin "1@2") (pinfunction "1_1@2") (pintype "passive"))
      (node (ref "PL") (pin "1") (pinfunction "P_1") (pintype "passive"))
      (node (ref "PL2") (pin "1") (pinfunction "P_1") (pintype "passive"))
      (node (ref "SV1") (pin "P$1") (pinfunction "1_P$1") (pintype "passive"))
      (node (ref "VD10") (pin "C") (pinfunction "C_C") (pintype "passive"))
    )
    (net (code "47") (name "RX") (class "Default")
      (node (ref "SV4") (pin "1") (pinfunction "1_1") (pintype "passive"))
      (node (ref "UART") (pin "3") (pinfunction "3_3") (pintype "passive"))
      (node (ref "X6") (pin "12") (pinfunction "12_12") (pintype "passive"))
    )
    (net (code "48") (name "SH+") (class "Default")
      (node (ref "C34") (pin "1") (pinfunction "1_1") (pintype "passive"))
      (node (ref "R35") (pin "1") (pinfunction "1_1") (pintype "passive"))
      (node (ref "X6") (pin "4") (pinfunction "4_4") (pintype "passive"))
    )
    (net (code "49") (name "SH-") (class "Default")
      (node (ref "C34") (pin "2") (pinfunction "2_2") (pintype "passive"))
      (node (ref "R36") (pin "1") (pinfunction "1_1") (pintype "passive"))
      (node (ref "X6") (pin "3") (pinfunction "3_3") (pintype "passive"))
    )
    (net (code "50") (name "S_VT2") (class "Default")
      (node (ref "C19") (pin "2") (pinfunction "2_2") (pintype "passive"))
      (node (ref "IC4") (pin "3") (pinfunction "-IN_3") (pintype "input"))
      (node (ref "R10") (pin "2") (pinfunction "2_2") (pintype "passive"))
      (node (ref "R11") (pin "2") (pinfunction "2_2") (pintype "passive"))
      (node (ref "R12") (pin "2") (pinfunction "2_2") (pintype "passive"))
      (node (ref "R13") (pin "2") (pinfunction "2_2") (pintype "passive"))
      (node (ref "R14") (pin "1") (pinfunction "1_1") (pintype "passive"))
      (node (ref "VT2") (pin "3") (pinfunction "S_3") (pintype "passive"))
    )
    (net (code "51") (name "TX") (class "Default")
      (node (ref "SV4") (pin "2") (pinfunction "2_2") (pintype "passive"))
      (node (ref "UART") (pin "5") (pinfunction "5_5") (pintype "passive"))
      (node (ref "X6") (pin "11") (pinfunction "11_11") (pintype "passive"))
    )
    (net (code "52") (name "unconnected-(COOLER-Pad3)") (class "Default")
      (node (ref "COOLER") (pin "3") (pinfunction "3_3") (pintype "passive"))
    )
    (net (code "53") (name "unconnected-(SV4-Pad9)") (class "Default")
      (node (ref "SV4") (pin "9") (pinfunction "9_9") (pintype "passive"))
    )
    (net (code "54") (name "unconnected-(VD11-C1A2-Pad3)") (class "Default")
      (node (ref "VD11") (pin "3") (pinfunction "C1A2_3") (pintype "passive"))
    )
    (net (code "55") (name "unconnected-(X5-Pad5)") (class "Default")
      (node (ref "X5") (pin "5") (pinfunction "5_5") (pintype "passive"))
    )
    (net (code "56") (name "unconnected-(X5-Pad8)") (class "Default")
      (node (ref "X5") (pin "8") (pinfunction "8_8") (pintype "passive"))
    )
    (net (code "57") (name "unconnected-(X5-Pad9)") (class "Default")
      (node (ref "X5") (pin "9") (pinfunction "9_9") (pintype "passive"))
    )
    (net (code "58") (name "unconnected-(X6-Pad1)") (class "Default")
      (node (ref "X6") (pin "1") (pinfunction "1_1") (pintype "passive"))
    )
    (net (code "59") (name "unconnected-(X6-Pad2)") (class "Default")
      (node (ref "X6") (pin "2") (pinfunction "2_2") (pintype "passive"))
    )
    (net (code "60") (name "unconnected-(X6-Pad5)") (class "Default")
      (node (ref "X6") (pin "5") (pinfunction "5_5") (pintype "passive"))
    )
    (net (code "61") (name "unconnected-(X6-Pad6)") (class "Default")
      (node (ref "X6") (pin "6") (pinfunction "6_6") (pintype "passive"))
    )
    (net (code "62") (name "unconnected-(X6-Pad7)") (class "Default")
      (node (ref "X6") (pin "7") (pinfunction "7_7") (pintype "passive"))
    )
    (net (code "63") (name "{slash}RESET") (class "Default")
      (node (ref "SV4") (pin "4") (pinfunction "4_4") (pintype "passive"))
      (node (ref "UART") (pin "7") (pinfunction "7_7") (pintype "passive"))
      (node (ref "X6") (pin "13") (pinfunction "13_13") (pintype "passive"))
    )
  )
)
